# M0_Express_ekho_shield.net
KiCad netlist of a schematic drawn in EAGLE
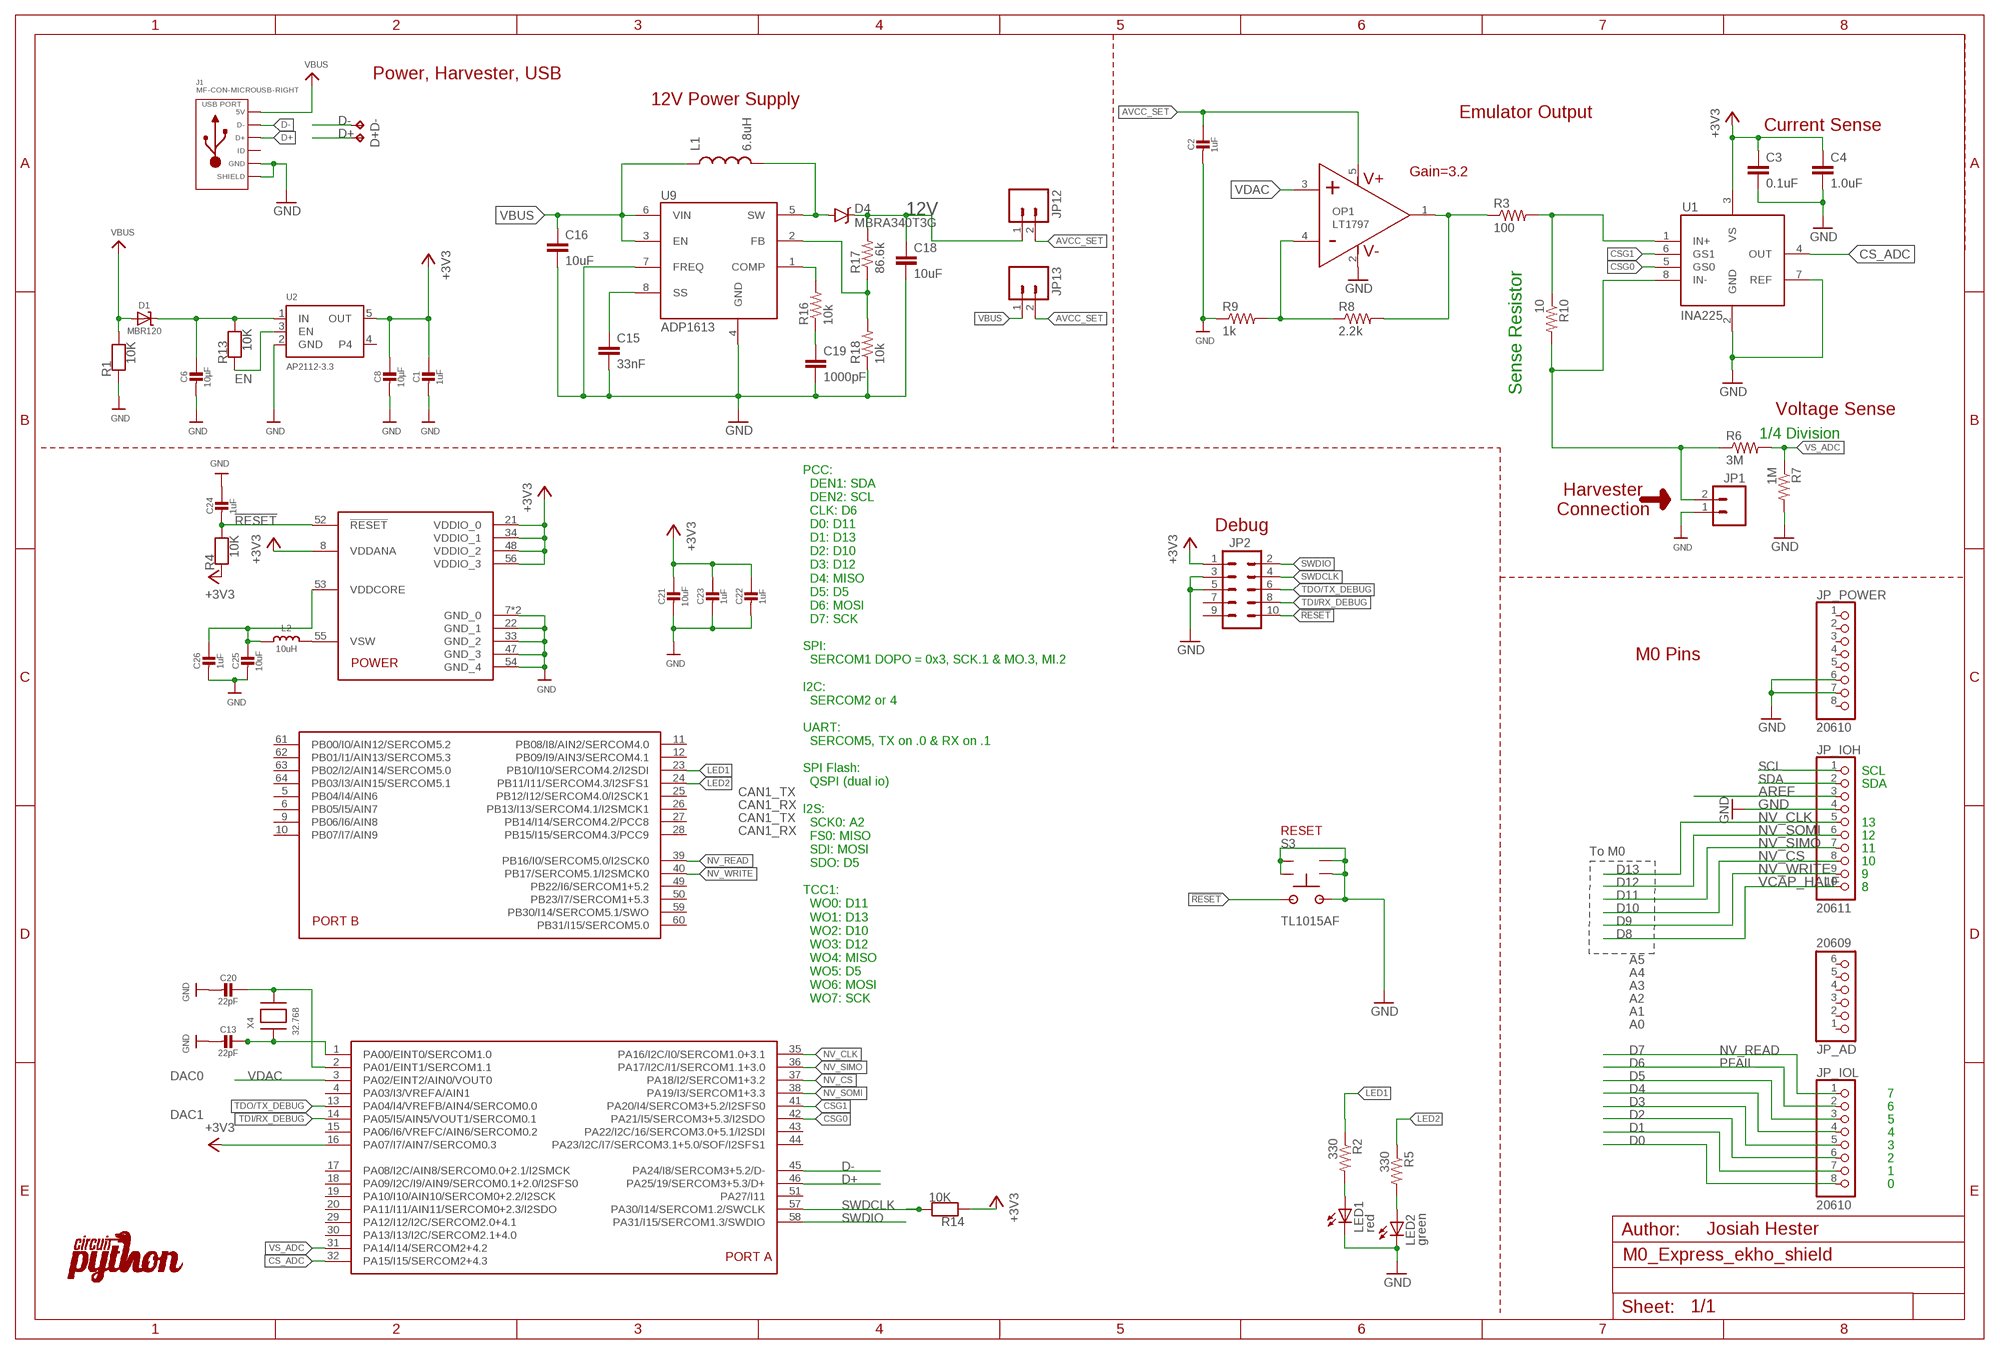
[diagram p0: schematic, sheet 1]

(export (version "E")
  (design (tool "Eeschema 10.0.6"))
  (components
    (comp (ref "C1")
      (value "1uF")
      (footprint "eagle-import:0603-NO")
      (libsource (lib "eagle-import") (part "CAP_CERAMIC0603_NO"))
    )
    (comp (ref "C2")
      (value "1uF")
      (footprint "eagle-import:0603-NO")
      (libsource (lib "eagle-import") (part "CAP_CERAMIC0603_NO"))
    )
    (comp (ref "C3")
      (value "0.1uF")
      (footprint "eagle-import:0603")
      (libsource (lib "eagle-import") (part "C-EU0603"))
    )
    (comp (ref "C4")
      (value "1.0uF")
      (footprint "eagle-import:0603")
      (libsource (lib "eagle-import") (part "C-EU0603"))
    )
    (comp (ref "C6")
      (value "10µF")
      (footprint "eagle-import:0805-NO")
      (libsource (lib "eagle-import") (part "CAP_CERAMIC0805-NOOUTLINE"))
    )
    (comp (ref "C8")
      (value "10µF")
      (footprint "eagle-import:0805-NO")
      (libsource (lib "eagle-import") (part "CAP_CERAMIC0805-NOOUTLINE"))
    )
    (comp (ref "C13")
      (value "22pF")
      (footprint "eagle-import:0603-NO")
      (libsource (lib "eagle-import") (part "CAP_CERAMIC0603_NO"))
    )
    (comp (ref "C15")
      (value "33nF")
      (footprint "eagle-import:0805")
      (fields (field (name "MPN") "C0805C333J5RACTU"))
      (libsource (lib "eagle-import") (part "CAP0805"))
    )
    (comp (ref "C16")
      (value "10uF")
      (footprint "eagle-import:0805")
      (fields (field (name "MPN") "EMK212BJ106KG-T "))
      (libsource (lib "eagle-import") (part "CAP0805"))
    )
    (comp (ref "C18")
      (value "10uF")
      (footprint "eagle-import:1206")
      (fields (field (name "MPN") "TMK316BJ106KL-T "))
      (libsource (lib "eagle-import") (part "CAP1206"))
    )
    (comp (ref "C19")
      (value "1000pF")
      (footprint "eagle-import:0805")
      (libsource (lib "eagle-import") (part "CAP0805"))
    )
    (comp (ref "C20")
      (value "22pF")
      (footprint "eagle-import:0603-NO")
      (libsource (lib "eagle-import") (part "CAP_CERAMIC0603_NO"))
    )
    (comp (ref "C21")
      (value "10uF")
      (footprint "eagle-import:0805-NO")
      (libsource (lib "eagle-import") (part "CAP_CERAMIC0805-NOOUTLINE"))
    )
    (comp (ref "C22")
      (value "1uF")
      (footprint "eagle-import:0603-NO")
      (libsource (lib "eagle-import") (part "CAP_CERAMIC0603_NO"))
    )
    (comp (ref "C23")
      (value "1uF")
      (footprint "eagle-import:0603-NO")
      (libsource (lib "eagle-import") (part "CAP_CERAMIC0603_NO"))
    )
    (comp (ref "C24")
      (value "1uF")
      (footprint "eagle-import:0603-NO")
      (libsource (lib "eagle-import") (part "CAP_CERAMIC0603_NO"))
    )
    (comp (ref "C25")
      (value "10uF")
      (footprint "eagle-import:0805-NO")
      (libsource (lib "eagle-import") (part "CAP_CERAMIC0805-NOOUTLINE"))
    )
    (comp (ref "C26")
      (value "1uF")
      (footprint "eagle-import:0603-NO")
      (libsource (lib "eagle-import") (part "CAP_CERAMIC0603_NO"))
    )
    (comp (ref "D+")
      (value "TPB1,27")
      (footprint "eagle-import:B1,27")
      (libsource (lib "eagle-import") (part "TPB1,27"))
    )
    (comp (ref "D-")
      (value "TPB1,27")
      (footprint "eagle-import:B1,27")
      (libsource (lib "eagle-import") (part "TPB1,27"))
    )
    (comp (ref "D1")
      (value "MBR120")
      (footprint "eagle-import:SOD-123")
      (libsource (lib "eagle-import") (part "DIODE-SCHOTTKYSOD-123"))
    )
    (comp (ref "D4")
      (value "MBRA340T3G")
      (footprint "eagle-import:SMA")
      (libsource (lib "eagle-import") (part "MBRA340T3G"))
    )
    (comp (ref "J1")
      (value "MF-CON-MICROUSB-RIGHT")
      (footprint "eagle-import:MICROUSB-RIGHT")
      (fields (field (name "HOUSEPART") "YES"))
      (libsource (lib "eagle-import") (part "USB_MICRO_RIGHT"))
    )
    (comp (ref "JP1")
      (value "M02LOCK")
      (footprint "eagle-import:1X02_LOCK")
      (libsource (lib "eagle-import") (part "M02LOCK"))
    )
    (comp (ref "JP2")
      (value "M05X21.27MM")
      (footprint "eagle-import:2X5_1.27MM")
      (fields (field (name "MPN") "3220-10-0100-00 "))
      (libsource (lib "eagle-import") (part "M05X21.27MM"))
    )
    (comp (ref "JP12")
      (value "M02LOCK")
      (footprint "eagle-import:1X02_LOCK")
      (libsource (lib "eagle-import") (part "M02LOCK"))
    )
    (comp (ref "JP13")
      (value "M02LOCK")
      (footprint "eagle-import:1X02_LOCK")
      (libsource (lib "eagle-import") (part "M02LOCK"))
    )
    (comp (ref "JP_AD")
      (value "20609")
      (footprint "eagle-import:1X06_OVALWAVE")
      (libsource (lib "eagle-import") (part "HEADER-1X6OVALWAVE"))
    )
    (comp (ref "JP_IOH")
      (value "20611")
      (footprint "eagle-import:1X10_OVALWAVE")
      (libsource (lib "eagle-import") (part "HEADER-1X10OVALWAVE"))
    )
    (comp (ref "JP_IOL")
      (value "20610")
      (footprint "eagle-import:1X08_OVALWAVE")
      (libsource (lib "eagle-import") (part "HEADER-1X8OVALWAVE"))
    )
    (comp (ref "JP_POWER")
      (value "20610")
      (footprint "eagle-import:1X08_OVALWAVE")
      (libsource (lib "eagle-import") (part "HEADER-1X8OVALWAVE"))
    )
    (comp (ref "L1")
      (value "6.8uH")
      (footprint "eagle-import:D03316P")
      (fields (field (name "MPN") "DO3316P"))
      (libsource (lib "eagle-import") (part "D03316P"))
    )
    (comp (ref "L2")
      (value "10uH")
      (footprint "eagle-import:INDUCTOR_1007")
      (libsource (lib "eagle-import") (part "INDUCTOR"))
    )
    (comp (ref "LED1")
      (value "red")
      (footprint "eagle-import:LED-0603")
      (libsource (lib "eagle-import") (part "LED0603"))
    )
    (comp (ref "LED2")
      (value "green")
      (footprint "eagle-import:LED-0603")
      (libsource (lib "eagle-import") (part "LED0603"))
    )
    (comp (ref "OP1")
      (value "LT1797")
      (footprint "eagle-import:TSOT23-8")
      (libsource (lib "eagle-import") (part "LT1797"))
    )
    (comp (ref "R1")
      (value "10K")
      (footprint "eagle-import:0603-NO")
      (libsource (lib "eagle-import") (part "RESISTOR_0603_NOOUT"))
    )
    (comp (ref "R2")
      (value "330")
      (footprint "eagle-import:0603")
      (libsource (lib "eagle-import") (part "R-EU0603"))
    )
    (comp (ref "R3")
      (value "100")
      (footprint "eagle-import:0805")
      (libsource (lib "eagle-import") (part "RESISTOR0805-RES"))
    )
    (comp (ref "R4")
      (value "10K")
      (footprint "eagle-import:0603-NO")
      (libsource (lib "eagle-import") (part "RESISTOR_0603_NOOUT"))
    )
    (comp (ref "R5")
      (value "330")
      (footprint "eagle-import:0603")
      (libsource (lib "eagle-import") (part "R-EU0603"))
    )
    (comp (ref "R6")
      (value "3M")
      (footprint "eagle-import:0603")
      (libsource (lib "eagle-import") (part "R-EU0603"))
    )
    (comp (ref "R7")
      (value "1M")
      (footprint "eagle-import:0603")
      (libsource (lib "eagle-import") (part "R-EU0603"))
    )
    (comp (ref "R8")
      (value "2.2k")
      (footprint "eagle-import:0603")
      (libsource (lib "eagle-import") (part "R-EU0603"))
    )
    (comp (ref "R9")
      (value "1k")
      (footprint "eagle-import:0603")
      (libsource (lib "eagle-import") (part "R-EU0603"))
    )
    (comp (ref "R10")
      (value "10")
      (footprint "eagle-import:0805")
      (libsource (lib "eagle-import") (part "RESISTOR0805-RES"))
    )
    (comp (ref "R13")
      (value "10K")
      (footprint "eagle-import:0603-NO")
      (libsource (lib "eagle-import") (part "RESISTOR_0603_NOOUT"))
    )
    (comp (ref "R14")
      (value "10K")
      (footprint "eagle-import:0603-NO")
      (libsource (lib "eagle-import") (part "RESISTOR_0603_NOOUT"))
    )
    (comp (ref "R16")
      (value "10k")
      (footprint "eagle-import:0805")
      (fields (field (name "MPN") "RC0805JR-0710KL "))
      (libsource (lib "eagle-import") (part "RESISTOR0805-RES"))
    )
    (comp (ref "R17")
      (value "86.6k")
      (footprint "eagle-import:0603")
      (fields (field (name "MPN") "RC0805FR-0786K6L "))
      (libsource (lib "eagle-import") (part "R-EU0603"))
    )
    (comp (ref "R18")
      (value "10k")
      (footprint "eagle-import:0603")
      (fields (field (name "MPN") "CRCW080510K0FKEA "))
      (libsource (lib "eagle-import") (part "R-EU0603"))
    )
    (comp (ref "S3")
      (value "TL1015AF")
      (footprint "eagle-import:TS1015")
      (fields (field (name "MPN") "TL1015AF160QG"))
      (libsource (lib "eagle-import") (part "TL1015AF"))
    )
    (comp (ref "U$1")
      (value "LOGO")
      (footprint "eagle-import:CIRCUITPYTHON-LOGO")
      (libsource (lib "eagle-import") (part "LOGO"))
    )
    (comp (ref "U$14")
      (value "ATSAMD51J")
      (footprint "eagle-import:PQFN64-1")
      (fields (field (name "DIGIKEY") "ATSAMD51J19A-MU-ND ") (field (name "MPN") "ATSAMD51J19A-MU "))
      (libsource (lib "eagle-import") (part "ATSAMD51J"))
    )
    (comp (ref "U1")
      (value "INA225")
      (footprint "eagle-import:MSOP8")
      (fields (field (name "MPN") "INA225AIDGKT"))
      (libsource (lib "eagle-import") (part "INA225"))
    )
    (comp (ref "U2")
      (value "AP2112-3.3")
      (footprint "eagle-import:SOT23-5")
      (libsource (lib "eagle-import") (part "VREG_SOT23-5"))
    )
    (comp (ref "U9")
      (value "ADP1613")
      (footprint "eagle-import:MSOP08")
      (fields (field (name "MPN") "ADP1613ARMZ-R7 "))
      (libsource (lib "eagle-import") (part "ADP1613"))
    )
    (comp (ref "X4")
      (value "32.768")
      (footprint "eagle-import:XTAL3215")
      (libsource (lib "eagle-import") (part "XTAL-3.2X1.5"))
    )
  )
  (nets
    (net (code "1") (name "+3V3") (class "Default")
      (node (ref "C1") (pin "1") (pinfunction "1_1") (pintype "passive"))
      (node (ref "C21") (pin "1") (pinfunction "1_1") (pintype "passive"))
      (node (ref "C22") (pin "1") (pinfunction "1_1") (pintype "passive"))
      (node (ref "C23") (pin "1") (pinfunction "1_1") (pintype "passive"))
      (node (ref "C3") (pin "1") (pinfunction "1_1") (pintype "passive"))
      (node (ref "C4") (pin "1") (pinfunction "1_1") (pintype "passive"))
      (node (ref "C8") (pin "1") (pinfunction "1_1") (pintype "passive"))
      (node (ref "JP2") (pin "1") (pinfunction "1_1") (pintype "passive"))
      (node (ref "R14") (pin "1") (pinfunction "1_1") (pintype "passive"))
      (node (ref "R4") (pin "1") (pinfunction "1_1") (pintype "passive"))
      (node (ref "U$14") (pin "16") (pinfunction "PA07/I7/AIN7/SERCOM0.3_16") (pintype "bidirectional"))
      (node (ref "U$14") (pin "21") (pinfunction "VDDIO_0_21") (pintype "bidirectional"))
      (node (ref "U$14") (pin "34") (pinfunction "VDDIO_1_34") (pintype "bidirectional"))
      (node (ref "U$14") (pin "48") (pinfunction "VDDIO_2_48") (pintype "bidirectional"))
      (node (ref "U$14") (pin "56") (pinfunction "VDDIO_3_56") (pintype "bidirectional"))
      (node (ref "U$14") (pin "8") (pinfunction "VDDANA_8") (pintype "bidirectional"))
      (node (ref "U1") (pin "3") (pinfunction "VS_3") (pintype "bidirectional"))
      (node (ref "U2") (pin "5") (pinfunction "OUT_5") (pintype "power_in"))
    )
    (net (code "2") (name "/12V") (class "Default")
      (node (ref "C18") (pin "1") (pinfunction "1_1") (pintype "passive"))
      (node (ref "D4") (pin "C") (pinfunction "C_C") (pintype "passive"))
      (node (ref "JP12") (pin "1") (pinfunction "1_1") (pintype "passive"))
      (node (ref "R17") (pin "2") (pinfunction "2_2") (pintype "passive"))
    )
    (net (code "3") (name "/AREF") (class "Default")
      (node (ref "JP_IOH") (pin "3") (pinfunction "3_3") (pintype "passive"))
    )
    (net (code "4") (name "/D0") (class "Default")
      (node (ref "JP_IOL") (pin "8") (pinfunction "8_8") (pintype "passive"))
    )
    (net (code "5") (name "/D1") (class "Default")
      (node (ref "JP_IOL") (pin "7") (pinfunction "7_7") (pintype "passive"))
    )
    (net (code "6") (name "/D2") (class "Default")
      (node (ref "JP_IOL") (pin "6") (pinfunction "6_6") (pintype "passive"))
    )
    (net (code "7") (name "/D3") (class "Default")
      (node (ref "JP_IOL") (pin "5") (pinfunction "5_5") (pintype "passive"))
    )
    (net (code "8") (name "/D4") (class "Default")
      (node (ref "JP_IOL") (pin "4") (pinfunction "4_4") (pintype "passive"))
    )
    (net (code "9") (name "/D5") (class "Default")
      (node (ref "JP_IOL") (pin "3") (pinfunction "3_3") (pintype "passive"))
    )
    (net (code "10") (name "/EN") (class "Default")
      (node (ref "R13") (pin "1") (pinfunction "1_1") (pintype "passive"))
      (node (ref "U2") (pin "3") (pinfunction "EN_3") (pintype "input"))
    )
    (net (code "11") (name "/PFAIL") (class "Default")
      (node (ref "JP_IOL") (pin "2") (pinfunction "2_2") (pintype "passive"))
    )
    (net (code "12") (name "/SCL") (class "Default")
      (node (ref "JP_IOH") (pin "1") (pinfunction "1_1") (pintype "passive"))
    )
    (net (code "13") (name "/SDA") (class "Default")
      (node (ref "JP_IOH") (pin "2") (pinfunction "2_2") (pintype "passive"))
    )
    (net (code "14") (name "/VCAP_HALF") (class "Default")
      (node (ref "JP_IOH") (pin "10") (pinfunction "10_10") (pintype "passive"))
    )
    (net (code "15") (name "/~{RESET}") (class "Default")
      (node (ref "C24") (pin "2") (pinfunction "2_2") (pintype "passive"))
      (node (ref "JP2") (pin "10") (pinfunction "10_10") (pintype "passive"))
      (node (ref "R4") (pin "2") (pinfunction "2_2") (pintype "passive"))
      (node (ref "S3") (pin "2") (pinfunction "2_2") (pintype "bidirectional"))
      (node (ref "U$14") (pin "52") (pinfunction "~{RESET}_52") (pintype "bidirectional"))
    )
    (net (code "16") (name "AVCC_SET") (class "Default")
      (node (ref "C2") (pin "1") (pinfunction "1_1") (pintype "passive"))
      (node (ref "JP12") (pin "2") (pinfunction "2_2") (pintype "passive"))
      (node (ref "JP13") (pin "2") (pinfunction "2_2") (pintype "passive"))
      (node (ref "OP1") (pin "5") (pinfunction "V+_5") (pintype "bidirectional"))
    )
    (net (code "17") (name "CSG0") (class "Default")
      (node (ref "U$14") (pin "42") (pinfunction "PA21/I5/SERCOM3+5.3/I2SDO_42") (pintype "bidirectional"))
      (node (ref "U1") (pin "5") (pinfunction "GS0_5") (pintype "bidirectional"))
    )
    (net (code "18") (name "CSG1") (class "Default")
      (node (ref "U$14") (pin "41") (pinfunction "PA20/I4/SERCOM3+5.2/I2SFS0_41") (pintype "bidirectional"))
      (node (ref "U1") (pin "6") (pinfunction "GS1_6") (pintype "bidirectional"))
    )
    (net (code "19") (name "CS_ADC") (class "Default")
      (node (ref "U$14") (pin "32") (pinfunction "PA15/I15/SERCOM2+4.3_32") (pintype "bidirectional"))
      (node (ref "U1") (pin "4") (pinfunction "OUT_4") (pintype "bidirectional"))
    )
    (net (code "20") (name "D+") (class "Default")
      (node (ref "D+") (pin "TP") (pinfunction "TP_TP") (pintype "input"))
      (node (ref "J1") (pin "3") (pinfunction "D+_3") (pintype "bidirectional"))
      (node (ref "U$14") (pin "46") (pinfunction "PA25/19/SERCOM3+5.3/D+_46") (pintype "bidirectional"))
    )
    (net (code "21") (name "D-") (class "Default")
      (node (ref "D-") (pin "TP") (pinfunction "TP_TP") (pintype "input"))
      (node (ref "J1") (pin "2") (pinfunction "D-_2") (pintype "bidirectional"))
      (node (ref "U$14") (pin "45") (pinfunction "PA24/I8/SERCOM3+5.2/D-_45") (pintype "bidirectional"))
    )
    (net (code "22") (name "GND") (class "Default")
      (node (ref "C1") (pin "2") (pinfunction "2_2") (pintype "passive"))
      (node (ref "C13") (pin "2") (pinfunction "2_2") (pintype "passive"))
      (node (ref "C15") (pin "2") (pinfunction "2_2") (pintype "passive"))
      (node (ref "C16") (pin "2") (pinfunction "2_2") (pintype "passive"))
      (node (ref "C18") (pin "2") (pinfunction "2_2") (pintype "passive"))
      (node (ref "C19") (pin "2") (pinfunction "2_2") (pintype "passive"))
      (node (ref "C2") (pin "2") (pinfunction "2_2") (pintype "passive"))
      (node (ref "C20") (pin "2") (pinfunction "2_2") (pintype "passive"))
      (node (ref "C21") (pin "2") (pinfunction "2_2") (pintype "passive"))
      (node (ref "C22") (pin "2") (pinfunction "2_2") (pintype "passive"))
      (node (ref "C23") (pin "2") (pinfunction "2_2") (pintype "passive"))
      (node (ref "C24") (pin "1") (pinfunction "1_1") (pintype "passive"))
      (node (ref "C25") (pin "2") (pinfunction "2_2") (pintype "passive"))
      (node (ref "C26") (pin "2") (pinfunction "2_2") (pintype "passive"))
      (node (ref "C3") (pin "2") (pinfunction "2_2") (pintype "passive"))
      (node (ref "C4") (pin "2") (pinfunction "2_2") (pintype "passive"))
      (node (ref "C6") (pin "2") (pinfunction "2_2") (pintype "passive"))
      (node (ref "C8") (pin "2") (pinfunction "2_2") (pintype "passive"))
      (node (ref "J1") (pin "5") (pinfunction "GND_5") (pintype "power_in"))
      (node (ref "J1") (pin "S1") (pinfunction "SLD_S1") (pintype "power_in"))
      (node (ref "J1") (pin "S2") (pinfunction "SLD_S2") (pintype "power_in"))
      (node (ref "J1") (pin "S3") (pinfunction "SLD_S3") (pintype "power_in"))
      (node (ref "J1") (pin "S4") (pinfunction "SLD_S4") (pintype "power_in"))
      (node (ref "J1") (pin "S5") (pinfunction "SLD_S5") (pintype "power_in"))
      (node (ref "J1") (pin "S6") (pinfunction "SLD_S6") (pintype "power_in"))
      (node (ref "JP1") (pin "1") (pinfunction "1_1") (pintype "passive"))
      (node (ref "JP2") (pin "3") (pinfunction "3_3") (pintype "passive"))
      (node (ref "JP2") (pin "5") (pinfunction "5_5") (pintype "passive"))
      (node (ref "JP_IOH") (pin "4") (pinfunction "4_4") (pintype "passive"))
      (node (ref "JP_POWER") (pin "6") (pinfunction "6_6") (pintype "passive"))
      (node (ref "JP_POWER") (pin "7") (pinfunction "7_7") (pintype "passive"))
      (node (ref "LED1") (pin "C") (pinfunction "C_C") (pintype "passive"))
      (node (ref "LED2") (pin "C") (pinfunction "C_C") (pintype "passive"))
      (node (ref "OP1") (pin "2") (pinfunction "V-_2") (pintype "bidirectional"))
      (node (ref "R1") (pin "1") (pinfunction "1_1") (pintype "passive"))
      (node (ref "R18") (pin "1") (pinfunction "1_1") (pintype "passive"))
      (node (ref "R7") (pin "2") (pinfunction "2_2") (pintype "passive"))
      (node (ref "R9") (pin "1") (pinfunction "1_1") (pintype "passive"))
      (node (ref "S3") (pin "1") (pinfunction "1_1") (pintype "bidirectional"))
      (node (ref "S3") (pin "G1") (pinfunction "GND_G1") (pintype "bidirectional"))
      (node (ref "S3") (pin "G2") (pinfunction "GND_G2") (pintype "bidirectional"))
      (node (ref "S3") (pin "G3") (pinfunction "GND_G3") (pintype "bidirectional"))
      (node (ref "S3") (pin "G4") (pinfunction "GND_G4") (pintype "bidirectional"))
      (node (ref "U$14") (pin "22") (pinfunction "GND_1_22") (pintype "bidirectional"))
      (node (ref "U$14") (pin "33") (pinfunction "GND_2_33") (pintype "bidirectional"))
      (node (ref "U$14") (pin "47") (pinfunction "GND_3_47") (pintype "bidirectional"))
      (node (ref "U$14") (pin "54") (pinfunction "GND_4_54") (pintype "bidirectional"))
      (node (ref "U$14") (pin "7") (pinfunction "GND_0_7") (pintype "bidirectional"))
      (node (ref "U$14") (pin "EXP") (pinfunction "GND_0_EXP") (pintype "bidirectional"))
      (node (ref "U1") (pin "2") (pinfunction "GND_2") (pintype "bidirectional"))
      (node (ref "U1") (pin "7") (pinfunction "REF_7") (pintype "bidirectional"))
      (node (ref "U2") (pin "2") (pinfunction "GND_2") (pintype "power_in"))
      (node (ref "U9") (pin "4") (pinfunction "GND_4") (pintype "bidirectional"))
      (node (ref "U9") (pin "7") (pinfunction "FREQ_7") (pintype "bidirectional"))
    )
    (net (code "23") (name "LED1") (class "Default")
      (node (ref "R2") (pin "1") (pinfunction "1_1") (pintype "passive"))
      (node (ref "U$14") (pin "23") (pinfunction "PB10/I10/SERCOM4.2/I2SDI_23") (pintype "bidirectional"))
    )
    (net (code "24") (name "LED2") (class "Default")
      (node (ref "R5") (pin "1") (pinfunction "1_1") (pintype "passive"))
      (node (ref "U$14") (pin "24") (pinfunction "PB11/I11/SERCOM4.3/I2SFS1_24") (pintype "bidirectional"))
    )
    (net (code "25") (name "NV_CLK") (class "Default")
      (node (ref "JP_IOH") (pin "5") (pinfunction "5_5") (pintype "passive"))
      (node (ref "U$14") (pin "35") (pinfunction "PA16/I2C/I0/SERCOM1.0+3.1_35") (pintype "bidirectional"))
    )
    (net (code "26") (name "NV_CS") (class "Default")
      (node (ref "JP_IOH") (pin "8") (pinfunction "8_8") (pintype "passive"))
      (node (ref "U$14") (pin "37") (pinfunction "PA18/I2/SERCOM1+3.2_37") (pintype "bidirectional"))
    )
    (net (code "27") (name "NV_READ") (class "Default")
      (node (ref "JP_IOL") (pin "1") (pinfunction "1_1") (pintype "passive"))
      (node (ref "U$14") (pin "39") (pinfunction "PB16/I0/SERCOM5.0/I2SCK0_39") (pintype "bidirectional"))
    )
    (net (code "28") (name "NV_SIMO") (class "Default")
      (node (ref "JP_IOH") (pin "7") (pinfunction "7_7") (pintype "passive"))
      (node (ref "U$14") (pin "36") (pinfunction "PA17/I2C/I1/SERCOM1.1+3.0_36") (pintype "bidirectional"))
    )
    (net (code "29") (name "NV_SOMI") (class "Default")
      (node (ref "JP_IOH") (pin "6") (pinfunction "6_6") (pintype "passive"))
      (node (ref "U$14") (pin "38") (pinfunction "PA19/I3/SERCOM1+3.3_38") (pintype "bidirectional"))
    )
    (net (code "30") (name "NV_WRITE") (class "Default")
      (node (ref "JP_IOH") (pin "9") (pinfunction "9_9") (pintype "passive"))
      (node (ref "U$14") (pin "40") (pinfunction "PB17/SERCOM5.1/I2SMCK0_40") (pintype "bidirectional"))
    )
    (net (code "31") (name "Net-(C19-Pad1)") (class "Default")
      (node (ref "C19") (pin "1") (pinfunction "1_1") (pintype "passive"))
      (node (ref "R16") (pin "1") (pinfunction "1_1") (pintype "passive"))
    )
    (net (code "32") (name "Net-(L1-2)") (class "Default")
      (node (ref "D4") (pin "A") (pinfunction "A_A") (pintype "passive"))
      (node (ref "L1") (pin "P$2") (pinfunction "2_P$2") (pintype "passive"))
      (node (ref "U9") (pin "5") (pinfunction "SW_5") (pintype "bidirectional"))
    )
    (net (code "33") (name "Net-(L2-1)") (class "Default")
      (node (ref "C25") (pin "1") (pinfunction "1_1") (pintype "passive"))
      (node (ref "C26") (pin "1") (pinfunction "1_1") (pintype "passive"))
      (node (ref "L2") (pin "P$1") (pinfunction "1_P$1") (pintype "passive"))
      (node (ref "U$14") (pin "53") (pinfunction "VDDCORE_53") (pintype "bidirectional"))
    )
    (net (code "34") (name "Net-(L2-2)") (class "Default")
      (node (ref "L2") (pin "P$2") (pinfunction "2_P$2") (pintype "passive"))
      (node (ref "U$14") (pin "55") (pinfunction "VSW_55") (pintype "bidirectional"))
    )
    (net (code "35") (name "Net-(LED1-PadA)") (class "Default")
      (node (ref "LED1") (pin "A") (pinfunction "A_A") (pintype "passive"))
      (node (ref "R2") (pin "2") (pinfunction "2_2") (pintype "passive"))
    )
    (net (code "36") (name "Net-(LED2-PadA)") (class "Default")
      (node (ref "LED2") (pin "A") (pinfunction "A_A") (pintype "passive"))
      (node (ref "R5") (pin "2") (pinfunction "2_2") (pintype "passive"))
    )
    (net (code "37") (name "Net-(OP1-IN-)") (class "Default")
      (node (ref "OP1") (pin "4") (pinfunction "IN-_4") (pintype "bidirectional"))
      (node (ref "R8") (pin "1") (pinfunction "1_1") (pintype "passive"))
      (node (ref "R9") (pin "2") (pinfunction "2_2") (pintype "passive"))
    )
    (net (code "38") (name "Net-(OP1-OUT)") (class "Default")
      (node (ref "OP1") (pin "1") (pinfunction "OUT_1") (pintype "bidirectional"))
      (node (ref "R3") (pin "1") (pinfunction "1_1") (pintype "passive"))
      (node (ref "R8") (pin "2") (pinfunction "2_2") (pintype "passive"))
    )
    (net (code "39") (name "Net-(U$14A-PA00{slash}EINT0{slash}SERCOM1.0)") (class "Default")
      (node (ref "C13") (pin "1") (pinfunction "1_1") (pintype "passive"))
      (node (ref "U$14") (pin "1") (pinfunction "PA00/EINT0/SERCOM1.0_1") (pintype "bidirectional"))
      (node (ref "X4") (pin "P$1") (pinfunction "P$1_P$1") (pintype "bidirectional"))
    )
    (net (code "40") (name "Net-(U$14A-PA01{slash}EINT1{slash}SERCOM1.1)") (class "Default")
      (node (ref "C20") (pin "1") (pinfunction "1_1") (pintype "passive"))
      (node (ref "U$14") (pin "2") (pinfunction "PA01/EINT1/SERCOM1.1_2") (pintype "bidirectional"))
      (node (ref "X4") (pin "P$2") (pinfunction "P$2_P$2") (pintype "bidirectional"))
    )
    (net (code "41") (name "Net-(U1-IN+)") (class "Default")
      (node (ref "R10") (pin "1") (pinfunction "1_1") (pintype "passive"))
      (node (ref "R3") (pin "2") (pinfunction "2_2") (pintype "passive"))
      (node (ref "U1") (pin "1") (pinfunction "IN+_1") (pintype "bidirectional"))
    )
    (net (code "42") (name "Net-(U1-IN-)") (class "Default")
      (node (ref "JP1") (pin "2") (pinfunction "2_2") (pintype "passive"))
      (node (ref "R10") (pin "2") (pinfunction "2_2") (pintype "passive"))
      (node (ref "R6") (pin "1") (pinfunction "1_1") (pintype "passive"))
      (node (ref "U1") (pin "8") (pinfunction "IN-_8") (pintype "bidirectional"))
    )
    (net (code "43") (name "Net-(U2-IN)") (class "Default")
      (node (ref "C6") (pin "1") (pinfunction "1_1") (pintype "passive"))
      (node (ref "D1") (pin "C") (pinfunction "C_C") (pintype "passive"))
      (node (ref "R13") (pin "2") (pinfunction "2_2") (pintype "passive"))
      (node (ref "U2") (pin "1") (pinfunction "IN_1") (pintype "power_in"))
    )
    (net (code "44") (name "Net-(U9-COMP)") (class "Default")
      (node (ref "R16") (pin "2") (pinfunction "2_2") (pintype "passive"))
      (node (ref "U9") (pin "1") (pinfunction "COMP_1") (pintype "bidirectional"))
    )
    (net (code "45") (name "Net-(U9-FB)") (class "Default")
      (node (ref "R17") (pin "1") (pinfunction "1_1") (pintype "passive"))
      (node (ref "R18") (pin "2") (pinfunction "2_2") (pintype "passive"))
      (node (ref "U9") (pin "2") (pinfunction "FB_2") (pintype "bidirectional"))
    )
    (net (code "46") (name "Net-(U9-SS)") (class "Default")
      (node (ref "C15") (pin "1") (pinfunction "1_1") (pintype "passive"))
      (node (ref "U9") (pin "8") (pinfunction "SS_8") (pintype "bidirectional"))
    )
    (net (code "47") (name "SWDCLK") (class "Default")
      (node (ref "JP2") (pin "4") (pinfunction "4_4") (pintype "passive"))
      (node (ref "R14") (pin "2") (pinfunction "2_2") (pintype "passive"))
      (node (ref "U$14") (pin "57") (pinfunction "PA30/I14/SERCOM1.2/SWCLK_57") (pintype "bidirectional"))
    )
    (net (code "48") (name "SWDIO") (class "Default")
      (node (ref "JP2") (pin "2") (pinfunction "2_2") (pintype "passive"))
      (node (ref "U$14") (pin "58") (pinfunction "PA31/I15/SERCOM1.3/SWDIO_58") (pintype "bidirectional"))
    )
    (net (code "49") (name "TDI{slash}RX_DEBUG") (class "Default")
      (node (ref "JP2") (pin "8") (pinfunction "8_8") (pintype "passive"))
      (node (ref "U$14") (pin "14") (pinfunction "PA05/I5/AIN5/VOUT1/SERCOM0.1_14") (pintype "bidirectional"))
    )
    (net (code "50") (name "TDO{slash}TX_DEBUG") (class "Default")
      (node (ref "JP2") (pin "6") (pinfunction "6_6") (pintype "passive"))
      (node (ref "U$14") (pin "13") (pinfunction "PA04/I4/VREFB/AIN4/SERCOM0.0_13") (pintype "bidirectional"))
    )
    (net (code "51") (name "VBUS") (class "Default")
      (node (ref "C16") (pin "1") (pinfunction "1_1") (pintype "passive"))
      (node (ref "D1") (pin "A") (pinfunction "A_A") (pintype "passive"))
      (node (ref "J1") (pin "1") (pinfunction "5V_1") (pintype "power_in"))
      (node (ref "JP13") (pin "1") (pinfunction "1_1") (pintype "passive"))
      (node (ref "L1") (pin "P$1") (pinfunction "1_P$1") (pintype "passive"))
      (node (ref "R1") (pin "2") (pinfunction "2_2") (pintype "passive"))
      (node (ref "U9") (pin "3") (pinfunction "EN_3") (pintype "bidirectional"))
      (node (ref "U9") (pin "6") (pinfunction "VIN_6") (pintype "bidirectional"))
    )
    (net (code "52") (name "VDAC") (class "Default")
      (node (ref "OP1") (pin "3") (pinfunction "IN+_3") (pintype "bidirectional"))
      (node (ref "U$14") (pin "3") (pinfunction "PA02/EINT2/AIN0/VOUT0_3") (pintype "bidirectional"))
    )
    (net (code "53") (name "VS_ADC") (class "Default")
      (node (ref "R6") (pin "2") (pinfunction "2_2") (pintype "passive"))
      (node (ref "R7") (pin "1") (pinfunction "1_1") (pintype "passive"))
      (node (ref "U$14") (pin "31") (pinfunction "PA14/I14/SERCOM2+4.2_31") (pintype "bidirectional"))
    )
    (net (code "54") (name "unconnected-(J1-ID-Pad4)") (class "Default")
      (node (ref "J1") (pin "4") (pinfunction "ID_4") (pintype "bidirectional"))
    )
    (net (code "55") (name "unconnected-(JP2-Pad7)") (class "Default")
      (node (ref "JP2") (pin "7") (pinfunction "7_7") (pintype "passive"))
    )
    (net (code "56") (name "unconnected-(JP2-Pad9)") (class "Default")
      (node (ref "JP2") (pin "9") (pinfunction "9_9") (pintype "passive"))
    )
    (net (code "57") (name "unconnected-(JP_AD-Pad1)") (class "Default")
      (node (ref "JP_AD") (pin "1") (pinfunction "1_1") (pintype "passive"))
    )
    (net (code "58") (name "unconnected-(JP_AD-Pad2)") (class "Default")
      (node (ref "JP_AD") (pin "2") (pinfunction "2_2") (pintype "passive"))
    )
    (net (code "59") (name "unconnected-(JP_AD-Pad3)") (class "Default")
      (node (ref "JP_AD") (pin "3") (pinfunction "3_3") (pintype "passive"))
    )
    (net (code "60") (name "unconnected-(JP_AD-Pad4)") (class "Default")
      (node (ref "JP_AD") (pin "4") (pinfunction "4_4") (pintype "passive"))
    )
    (net (code "61") (name "unconnected-(JP_AD-Pad5)") (class "Default")
      (node (ref "JP_AD") (pin "5") (pinfunction "5_5") (pintype "passive"))
    )
    (net (code "62") (name "unconnected-(JP_AD-Pad6)") (class "Default")
      (node (ref "JP_AD") (pin "6") (pinfunction "6_6") (pintype "passive"))
    )
    (net (code "63") (name "unconnected-(JP_POWER-Pad1)") (class "Default")
      (node (ref "JP_POWER") (pin "1") (pinfunction "1_1") (pintype "passive"))
    )
    (net (code "64") (name "unconnected-(JP_POWER-Pad2)") (class "Default")
      (node (ref "JP_POWER") (pin "2") (pinfunction "2_2") (pintype "passive"))
    )
    (net (code "65") (name "unconnected-(JP_POWER-Pad3)") (class "Default")
      (node (ref "JP_POWER") (pin "3") (pinfunction "3_3") (pintype "passive"))
    )
    (net (code "66") (name "unconnected-(JP_POWER-Pad4)") (class "Default")
      (node (ref "JP_POWER") (pin "4") (pinfunction "4_4") (pintype "passive"))
    )
    (net (code "67") (name "unconnected-(JP_POWER-Pad5)") (class "Default")
      (node (ref "JP_POWER") (pin "5") (pinfunction "5_5") (pintype "passive"))
    )
    (net (code "68") (name "unconnected-(JP_POWER-Pad8)") (class "Default")
      (node (ref "JP_POWER") (pin "8") (pinfunction "8_8") (pintype "passive"))
    )
    (net (code "69") (name "unconnected-(U$14A-PA03{slash}I3{slash}VREFA{slash}AIN1-Pad4)") (class "Default")
      (node (ref "U$14") (pin "4") (pinfunction "PA03/I3/VREFA/AIN1_4") (pintype "bidirectional"))
    )
    (net (code "70") (name "unconnected-(U$14A-PA06{slash}I6{slash}VREFC{slash}AIN6{slash}SERCOM0.2-Pad15)") (class "Default")
      (node (ref "U$14") (pin "15") (pinfunction "PA06/I6/VREFC/AIN6/SERCOM0.2_15") (pintype "bidirectional"))
    )
    (net (code "71") (name "unconnected-(U$14A-PA08{slash}I2C{slash}AIN8{slash}SERCOM0.0+2.1{slash}I2SMCK-Pad17)") (class "Default")
      (node (ref "U$14") (pin "17") (pinfunction "PA08/I2C/AIN8/SERCOM0.0+2.1/I2SMCK_17") (pintype "bidirectional"))
    )
    (net (code "72") (name "unconnected-(U$14A-PA09{slash}I2C{slash}I9{slash}AIN9{slash}SERCOM0.1+2.0{slash}I2SFS0-Pad18)") (class "Default")
      (node (ref "U$14") (pin "18") (pinfunction "PA09/I2C/I9/AIN9/SERCOM0.1+2.0/I2SFS0_18") (pintype "bidirectional"))
    )
    (net (code "73") (name "unconnected-(U$14A-PA10{slash}I10{slash}AIN10{slash}SERCOM0+2.2{slash}I2SCK-Pad19)") (class "Default")
      (node (ref "U$14") (pin "19") (pinfunction "PA10/I10/AIN10/SERCOM0+2.2/I2SCK_19") (pintype "bidirectional"))
    )
    (net (code "74") (name "unconnected-(U$14A-PA11{slash}I11{slash}AIN11{slash}SERCOM0+2.3{slash}I2SDO-Pad20)") (class "Default")
      (node (ref "U$14") (pin "20") (pinfunction "PA11/I11/AIN11/SERCOM0+2.3/I2SDO_20") (pintype "bidirectional"))
    )
    (net (code "75") (name "unconnected-(U$14A-PA12{slash}I12{slash}I2C{slash}SERCOM2.0+4.1-Pad29)") (class "Default")
      (node (ref "U$14") (pin "29") (pinfunction "PA12/I12/I2C/SERCOM2.0+4.1_29") (pintype "bidirectional"))
    )
    (net (code "76") (name "unconnected-(U$14A-PA13{slash}I13{slash}I2C{slash}SERCOM2.1+4.0-Pad30)") (class "Default")
      (node (ref "U$14") (pin "30") (pinfunction "PA13/I13/I2C/SERCOM2.1+4.0_30") (pintype "bidirectional"))
    )
    (net (code "77") (name "unconnected-(U$14A-PA22{slash}I2C{slash}16{slash}SERCOM3.0+5.1{slash}I2SDI-Pad43)") (class "Default")
      (node (ref "U$14") (pin "43") (pinfunction "PA22/I2C/16/SERCOM3.0+5.1/I2SDI_43") (pintype "bidirectional"))
    )
    (net (code "78") (name "unconnected-(U$14A-PA23{slash}I2C{slash}I7{slash}SERCOM3.1+5.0{slash}SOF{slash}I2SFS1-Pad44)") (class "Default")
      (node (ref "U$14") (pin "44") (pinfunction "PA23/I2C/I7/SERCOM3.1+5.0/SOF/I2SFS1_44") (pintype "bidirectional"))
    )
    (net (code "79") (name "unconnected-(U$14A-PA27{slash}I11-Pad51)") (class "Default")
      (node (ref "U$14") (pin "51") (pinfunction "PA27/I11_51") (pintype "bidirectional"))
    )
    (net (code "80") (name "unconnected-(U$14B-PB00{slash}I0{slash}AIN12{slash}SERCOM5.2-Pad61)") (class "Default")
      (node (ref "U$14") (pin "61") (pinfunction "PB00/I0/AIN12/SERCOM5.2_61") (pintype "bidirectional"))
    )
    (net (code "81") (name "unconnected-(U$14B-PB01{slash}I1{slash}AIN13{slash}SERCOM5.3-Pad62)") (class "Default")
      (node (ref "U$14") (pin "62") (pinfunction "PB01/I1/AIN13/SERCOM5.3_62") (pintype "bidirectional"))
    )
    (net (code "82") (name "unconnected-(U$14B-PB02{slash}I2{slash}AIN14{slash}SERCOM5.0-Pad63)") (class "Default")
      (node (ref "U$14") (pin "63") (pinfunction "PB02/I2/AIN14/SERCOM5.0_63") (pintype "bidirectional"))
    )
    (net (code "83") (name "unconnected-(U$14B-PB03{slash}I3{slash}AIN15{slash}SERCOM5.1-Pad64)") (class "Default")
      (node (ref "U$14") (pin "64") (pinfunction "PB03/I3/AIN15/SERCOM5.1_64") (pintype "bidirectional"))
    )
    (net (code "84") (name "unconnected-(U$14B-PB04{slash}I4{slash}AIN6-Pad5)") (class "Default")
      (node (ref "U$14") (pin "5") (pinfunction "PB04/I4/AIN6_5") (pintype "bidirectional"))
    )
    (net (code "85") (name "unconnected-(U$14B-PB05{slash}I5{slash}AIN7-Pad6)") (class "Default")
      (node (ref "U$14") (pin "6") (pinfunction "PB05/I5/AIN7_6") (pintype "bidirectional"))
    )
    (net (code "86") (name "unconnected-(U$14B-PB06{slash}I6{slash}AIN8-Pad9)") (class "Default")
      (node (ref "U$14") (pin "9") (pinfunction "PB06/I6/AIN8_9") (pintype "bidirectional"))
    )
    (net (code "87") (name "unconnected-(U$14B-PB07{slash}I7{slash}AIN9-Pad10)") (class "Default")
      (node (ref "U$14") (pin "10") (pinfunction "PB07/I7/AIN9_10") (pintype "bidirectional"))
    )
    (net (code "88") (name "unconnected-(U$14B-PB08{slash}I8{slash}AIN2{slash}SERCOM4.0-Pad11)") (class "Default")
      (node (ref "U$14") (pin "11") (pinfunction "PB08/I8/AIN2/SERCOM4.0_11") (pintype "bidirectional"))
    )
    (net (code "89") (name "unconnected-(U$14B-PB09{slash}I9{slash}AIN3{slash}SERCOM4.1-Pad12)") (class "Default")
      (node (ref "U$14") (pin "12") (pinfunction "PB09/I9/AIN3/SERCOM4.1_12") (pintype "bidirectional"))
    )
    (net (code "90") (name "unconnected-(U$14B-PB12{slash}I12{slash}SERCOM4.0{slash}I2SCK1-Pad25)") (class "Default")
      (node (ref "U$14") (pin "25") (pinfunction "PB12/I12/SERCOM4.0/I2SCK1_25") (pintype "bidirectional"))
    )
    (net (code "91") (name "unconnected-(U$14B-PB13{slash}I13{slash}SERCOM4.1{slash}I2SMCK1-Pad26)") (class "Default")
      (node (ref "U$14") (pin "26") (pinfunction "PB13/I13/SERCOM4.1/I2SMCK1_26") (pintype "bidirectional"))
    )
    (net (code "92") (name "unconnected-(U$14B-PB14{slash}I14{slash}SERCOM4.2{slash}PCC8-Pad27)") (class "Default")
      (node (ref "U$14") (pin "27") (pinfunction "PB14/I14/SERCOM4.2/PCC8_27") (pintype "bidirectional"))
    )
    (net (code "93") (name "unconnected-(U$14B-PB15{slash}I15{slash}SERCOM4.3{slash}PCC9-Pad28)") (class "Default")
      (node (ref "U$14") (pin "28") (pinfunction "PB15/I15/SERCOM4.3/PCC9_28") (pintype "bidirectional"))
    )
    (net (code "94") (name "unconnected-(U$14B-PB22{slash}I6{slash}SERCOM1+5.2-Pad49)") (class "Default")
      (node (ref "U$14") (pin "49") (pinfunction "PB22/I6/SERCOM1+5.2_49") (pintype "bidirectional"))
    )
    (net (code "95") (name "unconnected-(U$14B-PB23{slash}I7{slash}SERCOM1+5.3-Pad50)") (class "Default")
      (node (ref "U$14") (pin "50") (pinfunction "PB23/I7/SERCOM1+5.3_50") (pintype "bidirectional"))
    )
    (net (code "96") (name "unconnected-(U$14B-PB30{slash}I14{slash}SERCOM5.1{slash}SWO-Pad59)") (class "Default")
      (node (ref "U$14") (pin "59") (pinfunction "PB30/I14/SERCOM5.1/SWO_59") (pintype "bidirectional"))
    )
    (net (code "97") (name "unconnected-(U$14B-PB31{slash}I15{slash}SERCOM5.0-Pad60)") (class "Default")
      (node (ref "U$14") (pin "60") (pinfunction "PB31/I15/SERCOM5.0_60") (pintype "bidirectional"))
    )
    (net (code "98") (name "unconnected-(U2-P4-Pad4)") (class "Default")
      (node (ref "U2") (pin "4") (pinfunction "P4_4") (pintype "bidirectional"))
    )
  )
)
